# MCU.net
KiCad netlist of a schematic drawn in Altium Designer
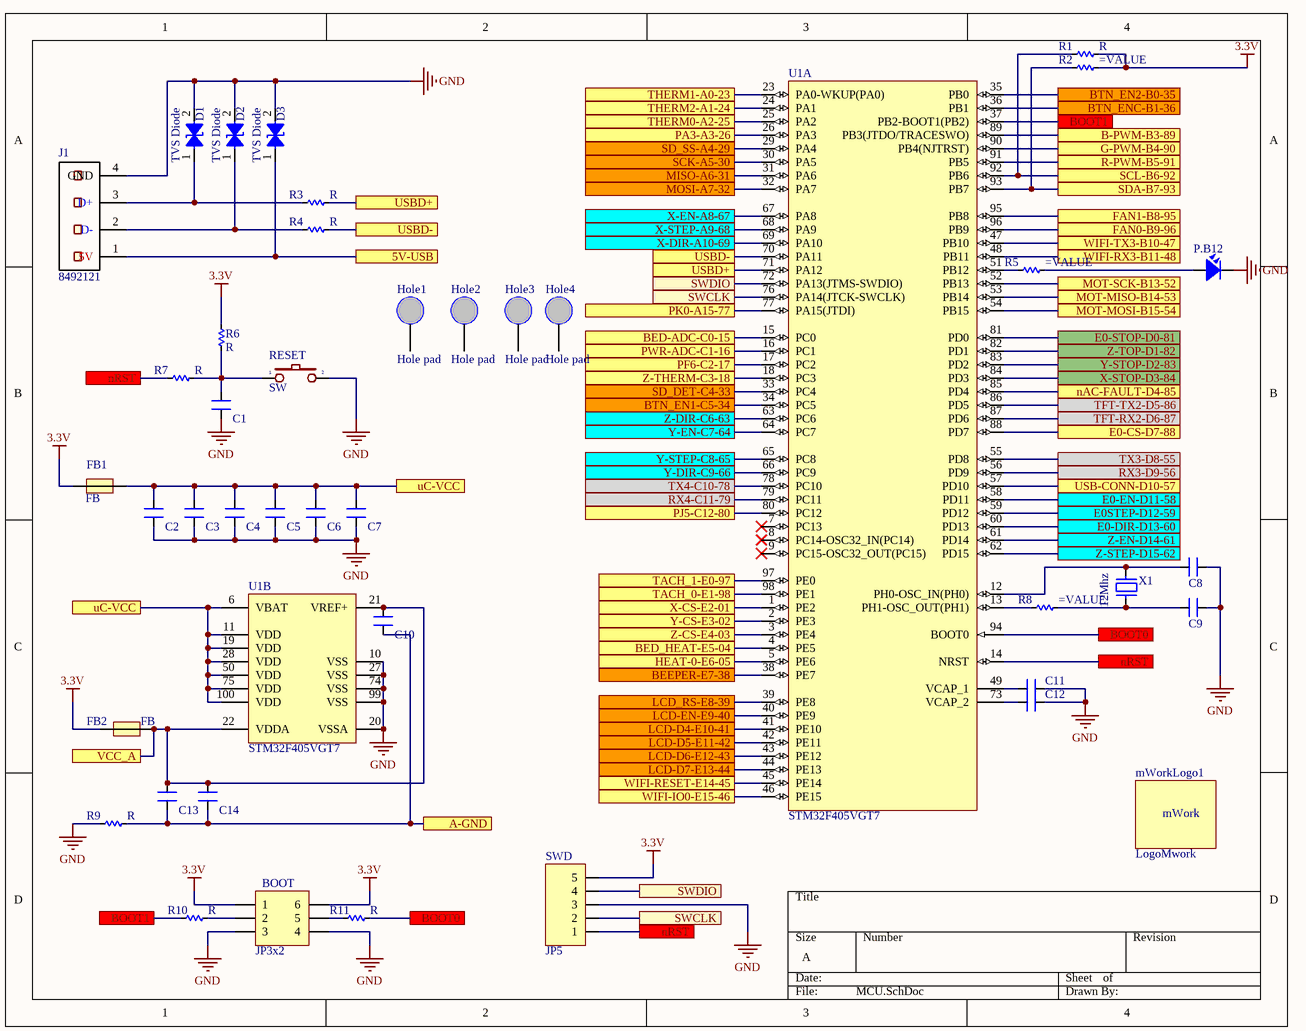
[diagram p0: MCU.SchDoc]

(export (version "E")
  (design (tool "Eeschema 10.0.6"))
  (components
    (comp (ref "BOOT")
      (value "JP3x2")
      (footprint "JP3-D2T")
      (description "WR-PHD 2.54 mm Dual Socket Header")
      (fields
        (field (name "MANUFACTURER") "Würth Elektronik eiSos GmbH")
        (field (name "PARTNO") "61300621821")
        (field (name "CREATED BY") "Karrer Zheng")
      )
      (libsource (lib "BanLinhKien") (part "JP3x2"))
    )
    (comp (ref "C1") (value "CN") (footprint "CN-SMD-0603_big") (libsource (lib "nhan") (part "CN")))
    (comp (ref "C2") (value "CN") (footprint "CN-SMD-0603_big") (libsource (lib "nhan") (part "CN")))
    (comp (ref "C3") (value "CN") (footprint "CN-SMD-0603_big") (libsource (lib "nhan") (part "CN")))
    (comp (ref "C4") (value "CN") (footprint "CN-SMD-0603_big") (libsource (lib "nhan") (part "CN")))
    (comp (ref "C5") (value "CN") (footprint "CN-SMD-0603_big") (libsource (lib "nhan") (part "CN")))
    (comp (ref "C6") (value "CN") (footprint "CN-SMD-0603_big") (libsource (lib "nhan") (part "CN")))
    (comp (ref "C7") (value "CN") (footprint "CN-SMD-0603_big") (libsource (lib "nhan") (part "CN")))
    (comp (ref "C8") (value "CN") (footprint "CN-SMD-0603_big") (libsource (lib "nhan") (part "CN")))
    (comp (ref "C9") (value "CN") (footprint "CN-SMD-0603_big") (libsource (lib "nhan") (part "CN")))
    (comp (ref "C10") (value "CN") (footprint "CN-SMD-0603_big") (libsource (lib "nhan") (part "CN")))
    (comp (ref "C11") (value "CN") (footprint "CN-SMD-0603_big") (libsource (lib "nhan") (part "CN")))
    (comp (ref "C12") (value "CN") (footprint "CN-SMD-0603_big") (libsource (lib "nhan") (part "CN")))
    (comp (ref "C13") (value "CN") (footprint "CN-SMD-0603_big") (libsource (lib "nhan") (part "CN")))
    (comp (ref "C14") (value "CN") (footprint "CN-SMD-0603_big") (libsource (lib "nhan") (part "CN")))
    (comp (ref "D1")
      (value "TVS Diode")
      (footprint "DIO-SMD-214AC")
      (description "SMAJ5.0A")
      (libsource (lib "nhan") (part "TVS Diode"))
    )
    (comp (ref "D2")
      (value "TVS Diode")
      (footprint "DIO-SMD-214AC")
      (description "SMAJ5.0A")
      (libsource (lib "nhan") (part "TVS Diode"))
    )
    (comp (ref "D3")
      (value "TVS Diode")
      (footprint "DIO-SMD-214AC")
      (description "SMAJ5.0A")
      (libsource (lib "nhan") (part "TVS Diode"))
    )
    (comp (ref "FB1") (value "FB") (footprint "Capacitor_805") (libsource (lib "nhan") (part "FB")))
    (comp (ref "FB2") (value "FB") (footprint "Capacitor_805") (libsource (lib "nhan") (part "FB")))
    (comp (ref "Hole1") (value "Hole pad") (footprint "HolePad1") (libsource (lib "nhan") (part "Hole pad")))
    (comp (ref "Hole2") (value "Hole pad") (footprint "HolePad1") (libsource (lib "nhan") (part "Hole pad")))
    (comp (ref "Hole3") (value "Hole pad") (footprint "HolePad1") (libsource (lib "nhan") (part "Hole pad")))
    (comp (ref "Hole4") (value "Hole pad") (footprint "HolePad1") (libsource (lib "nhan") (part "Hole pad")))
    (comp (ref "J1")
      (value "8492121")
      (footprint "USB-C2")
      (description "THT USB 2.0 A Connector WE-EPLE")
      (fields
        (field (name "MANUFACTURER") "Würth Elektronik eiSos GmbH")
        (field (name "CREATED BY") "Christin Otto")
      )
      (libsource (lib "nhan") (part "USB-4"))
    )
    (comp (ref "mWorkLogo1")
      (value "LogoMwork")
      (footprint "LogoMwork15*6")
      (libsource (lib "nhan") (part "LogoMwork"))
    )
    (comp (ref "P.B12") (value "LED") (footprint "LED-RED-0805") (libsource (lib "LIBRARY") (part "LED SMD")))
    (comp (ref "R1") (value "R") (footprint "RES-SMD-0603_BIG") (libsource (lib "nhan") (part "R")))
    (comp (ref "R2") (value "~") (footprint "RES-SMD-0603_BIG") (libsource (lib "nhan") (part "R")))
    (comp (ref "R3") (value "R") (footprint "RES-SMD-0603_BIG") (libsource (lib "nhan") (part "R")))
    (comp (ref "R4") (value "R") (footprint "RES-SMD-0603_BIG") (libsource (lib "nhan") (part "R")))
    (comp (ref "R5") (value "~") (footprint "RES-SMD-0603_BIG") (libsource (lib "nhan") (part "R")))
    (comp (ref "R6") (value "R") (footprint "RES-SMD-0603_BIG") (libsource (lib "nhan") (part "R")))
    (comp (ref "R7") (value "R") (footprint "RES-SMD-0603_BIG") (libsource (lib "nhan") (part "R")))
    (comp (ref "R8") (value "~") (footprint "RES-SMD-0603_BIG") (libsource (lib "nhan") (part "R")))
    (comp (ref "R9") (value "R") (footprint "RES-SMD-0603_BIG") (libsource (lib "nhan") (part "R")))
    (comp (ref "R10") (value "R") (footprint "RES-SMD-0603_BIG") (libsource (lib "nhan") (part "R")))
    (comp (ref "R11") (value "R") (footprint "RES-SMD-0603_BIG") (libsource (lib "nhan") (part "R")))
    (comp (ref "RESET")
      (value "SW")
      (footprint "SW1-SMD")
      (description "Switch button 2 pin")
      (libsource (lib "LIBRARY") (part "SW2"))
    )
    (comp (ref "SWD")
      (value "JP5")
      (footprint "JP5-D1T")
      (description "WR-PHD 2.54 mm Angled Socket Header")
      (fields
        (field (name "MANUFACTURER") "Würth Elektronik eiSos GmbH")
        (field (name "PARTNO") "613005143121")
        (field (name "CREATED BY") "Karrer Zheng")
      )
      (libsource (lib "nhan") (part "JP5"))
    )
    (comp (ref "U1")
      (value "STM32F405VGT7")
      (footprint "STM-LQFP100_N")
      (fields (field (name "MANUFACTURER") "STMicroelectronics"))
      (libsource (lib "STMicroelectronics STM32 F4") (part "STM32F405VGT7"))
    )
    (comp (ref "X1")
      (value "12Mhz")
      (footprint "XT2")
      (description "Crystal, 32.768 KHz, -40 to 85 degC, 3.2 x 1.5 x 0.9 mm SMD")
      (libsource (lib "LIBRARY") (part "XT2"))
    )
  )
  (nets
    (net (code "1") (name "/5V-USB") (class "Default")
      (node (ref "D3") (pin "1") (pinfunction "I/O_1_1") (pintype "passive"))
      (node (ref "J1") (pin "1") (pinfunction "5V_1") (pintype "passive"))
    )
    (net (code "2") (name "/A-GND") (class "Default")
      (node (ref "C10") (pin "1") (pinfunction "1_1") (pintype "passive"))
      (node (ref "C13") (pin "1") (pinfunction "1_1") (pintype "passive"))
      (node (ref "C14") (pin "1") (pinfunction "1_1") (pintype "passive"))
      (node (ref "R9") (pin "1") (pinfunction "1_1") (pintype "passive"))
    )
    (net (code "3") (name "/B-PWM-B3-89") (class "Default")
      (node (ref "U1") (pin "89") (pinfunction "PB3(JTDO/TRACESWO)_89") (pintype "bidirectional"))
    )
    (net (code "4") (name "/BED-ADC-C0-15") (class "Default")
      (node (ref "U1") (pin "15") (pinfunction "PC0_15") (pintype "bidirectional"))
    )
    (net (code "5") (name "/BED_HEAT-E5-04") (class "Default")
      (node (ref "U1") (pin "4") (pinfunction "PE5_4") (pintype "bidirectional"))
    )
    (net (code "6") (name "/BEEPER-E7-38") (class "Default")
      (node (ref "U1") (pin "38") (pinfunction "PE7_38") (pintype "bidirectional"))
    )
    (net (code "7") (name "/BOOT0") (class "Default")
      (node (ref "R11") (pin "1") (pinfunction "1_1") (pintype "passive"))
      (node (ref "U1") (pin "94") (pinfunction "BOOT0_94") (pintype "input"))
    )
    (net (code "8") (name "/BOOT1") (class "Default")
      (node (ref "R10") (pin "2") (pinfunction "2_2") (pintype "passive"))
      (node (ref "U1") (pin "37") (pinfunction "PB2-BOOT1(PB2)_37") (pintype "bidirectional"))
    )
    (net (code "9") (name "/BTN_EN1-C5-34") (class "Default")
      (node (ref "U1") (pin "34") (pinfunction "PC5_34") (pintype "bidirectional"))
    )
    (net (code "10") (name "/BTN_EN2-B0-35") (class "Default")
      (node (ref "U1") (pin "35") (pinfunction "PB0_35") (pintype "bidirectional"))
    )
    (net (code "11") (name "/BTN_ENC-B1-36") (class "Default")
      (node (ref "U1") (pin "36") (pinfunction "PB1_36") (pintype "bidirectional"))
    )
    (net (code "12") (name "/E0-CS-D7-88") (class "Default")
      (node (ref "U1") (pin "88") (pinfunction "PD7_88") (pintype "bidirectional"))
    )
    (net (code "13") (name "/E0-DIR-D13-60") (class "Default")
      (node (ref "U1") (pin "60") (pinfunction "PD13_60") (pintype "bidirectional"))
    )
    (net (code "14") (name "/E0-EN-D11-58") (class "Default")
      (node (ref "U1") (pin "58") (pinfunction "PD11_58") (pintype "bidirectional"))
    )
    (net (code "15") (name "/E0-STOP-D0-81") (class "Default")
      (node (ref "U1") (pin "81") (pinfunction "PD0_81") (pintype "bidirectional"))
    )
    (net (code "16") (name "/E0STEP-D12-59") (class "Default")
      (node (ref "U1") (pin "59") (pinfunction "PD12_59") (pintype "bidirectional"))
    )
    (net (code "17") (name "/FAN0-B9-96") (class "Default")
      (node (ref "U1") (pin "96") (pinfunction "PB9_96") (pintype "bidirectional"))
    )
    (net (code "18") (name "/FAN1-B8-95") (class "Default")
      (node (ref "U1") (pin "95") (pinfunction "PB8_95") (pintype "bidirectional"))
    )
    (net (code "19") (name "/G-PWM-B4-90") (class "Default")
      (node (ref "U1") (pin "90") (pinfunction "PB4(NJTRST)_90") (pintype "bidirectional"))
    )
    (net (code "20") (name "/HEAT-0-E6-05") (class "Default")
      (node (ref "U1") (pin "5") (pinfunction "PE6_5") (pintype "bidirectional"))
    )
    (net (code "21") (name "/LCD-D4-E10-41") (class "Default")
      (node (ref "U1") (pin "41") (pinfunction "PE10_41") (pintype "bidirectional"))
    )
    (net (code "22") (name "/LCD-D5-E11-42") (class "Default")
      (node (ref "U1") (pin "42") (pinfunction "PE11_42") (pintype "bidirectional"))
    )
    (net (code "23") (name "/LCD-D6-E12-43") (class "Default")
      (node (ref "U1") (pin "43") (pinfunction "PE12_43") (pintype "bidirectional"))
    )
    (net (code "24") (name "/LCD-D7-E13-44") (class "Default")
      (node (ref "U1") (pin "44") (pinfunction "PE13_44") (pintype "bidirectional"))
    )
    (net (code "25") (name "/LCD-EN-E9-40") (class "Default")
      (node (ref "U1") (pin "40") (pinfunction "PE9_40") (pintype "bidirectional"))
    )
    (net (code "26") (name "/LCD_RS-E8-39") (class "Default")
      (node (ref "U1") (pin "39") (pinfunction "PE8_39") (pintype "bidirectional"))
    )
    (net (code "27") (name "/MISO-A6-31") (class "Default")
      (node (ref "U1") (pin "31") (pinfunction "PA6_31") (pintype "bidirectional"))
    )
    (net (code "28") (name "/MOSI-A7-32") (class "Default")
      (node (ref "U1") (pin "32") (pinfunction "PA7_32") (pintype "bidirectional"))
    )
    (net (code "29") (name "/MOT-MISO-B14-53") (class "Default")
      (node (ref "U1") (pin "53") (pinfunction "PB14_53") (pintype "bidirectional"))
    )
    (net (code "30") (name "/MOT-MOSI-B15-54") (class "Default")
      (node (ref "U1") (pin "54") (pinfunction "PB15_54") (pintype "bidirectional"))
    )
    (net (code "31") (name "/MOT-SCK-B13-52") (class "Default")
      (node (ref "U1") (pin "52") (pinfunction "PB13_52") (pintype "bidirectional"))
    )
    (net (code "32") (name "/PA3-A3-26") (class "Default")
      (node (ref "U1") (pin "26") (pinfunction "PA3_26") (pintype "bidirectional"))
    )
    (net (code "33") (name "/PF6-C2-17") (class "Default")
      (node (ref "U1") (pin "17") (pinfunction "PC2_17") (pintype "bidirectional"))
    )
    (net (code "34") (name "/PJ5-C12-80") (class "Default")
      (node (ref "U1") (pin "80") (pinfunction "PC12_80") (pintype "bidirectional"))
    )
    (net (code "35") (name "/PK0-A15-77") (class "Default")
      (node (ref "U1") (pin "77") (pinfunction "PA15(JTDI)_77") (pintype "bidirectional"))
    )
    (net (code "36") (name "/PWR-ADC-C1-16") (class "Default")
      (node (ref "U1") (pin "16") (pinfunction "PC1_16") (pintype "bidirectional"))
    )
    (net (code "37") (name "/R-PWM-B5-91") (class "Default")
      (node (ref "U1") (pin "91") (pinfunction "PB5_91") (pintype "bidirectional"))
    )
    (net (code "38") (name "/RX3-D9-56") (class "Default")
      (node (ref "U1") (pin "56") (pinfunction "PD9_56") (pintype "bidirectional"))
    )
    (net (code "39") (name "/RX4-C11-79") (class "Default")
      (node (ref "U1") (pin "79") (pinfunction "PC11_79") (pintype "bidirectional"))
    )
    (net (code "40") (name "/SCK-A5-30") (class "Default")
      (node (ref "U1") (pin "30") (pinfunction "PA5_30") (pintype "bidirectional"))
    )
    (net (code "41") (name "/SCL-B6-92") (class "Default")
      (node (ref "R1") (pin "1") (pinfunction "1_1") (pintype "passive"))
      (node (ref "U1") (pin "92") (pinfunction "PB6_92") (pintype "bidirectional"))
    )
    (net (code "42") (name "/SDA-B7-93") (class "Default")
      (node (ref "R2") (pin "1") (pinfunction "1_1") (pintype "passive"))
      (node (ref "U1") (pin "93") (pinfunction "PB7_93") (pintype "bidirectional"))
    )
    (net (code "43") (name "/SD_DET-C4-33") (class "Default")
      (node (ref "U1") (pin "33") (pinfunction "PC4_33") (pintype "bidirectional"))
    )
    (net (code "44") (name "/SD_SS-A4-29") (class "Default")
      (node (ref "U1") (pin "29") (pinfunction "PA4_29") (pintype "bidirectional"))
    )
    (net (code "45") (name "/SWCLK") (class "Default")
      (node (ref "SWD") (pin "2") (pinfunction "2_2") (pintype "passive"))
      (node (ref "U1") (pin "76") (pinfunction "PA14(JTCK-SWCLK)_76") (pintype "bidirectional"))
    )
    (net (code "46") (name "/SWDIO") (class "Default")
      (node (ref "SWD") (pin "4") (pinfunction "4_4") (pintype "passive"))
      (node (ref "U1") (pin "72") (pinfunction "PA13(JTMS-SWDIO)_72") (pintype "bidirectional"))
    )
    (net (code "47") (name "/TACH_0-E1-98") (class "Default")
      (node (ref "U1") (pin "98") (pinfunction "PE1_98") (pintype "bidirectional"))
    )
    (net (code "48") (name "/TACH_1-E0-97") (class "Default")
      (node (ref "U1") (pin "97") (pinfunction "PE0_97") (pintype "bidirectional"))
    )
    (net (code "49") (name "/TFT-RX2-D6-87") (class "Default")
      (node (ref "U1") (pin "87") (pinfunction "PD6_87") (pintype "bidirectional"))
    )
    (net (code "50") (name "/TFT-TX2-D5-86") (class "Default")
      (node (ref "U1") (pin "86") (pinfunction "PD5_86") (pintype "bidirectional"))
    )
    (net (code "51") (name "/THERM0-A2-25") (class "Default")
      (node (ref "U1") (pin "25") (pinfunction "PA2_25") (pintype "bidirectional"))
    )
    (net (code "52") (name "/THERM1-A0-23") (class "Default")
      (node (ref "U1") (pin "23") (pinfunction "PA0-WKUP(PA0)_23") (pintype "bidirectional"))
    )
    (net (code "53") (name "/THERM2-A1-24") (class "Default")
      (node (ref "U1") (pin "24") (pinfunction "PA1_24") (pintype "bidirectional"))
    )
    (net (code "54") (name "/TX3-D8-55") (class "Default")
      (node (ref "U1") (pin "55") (pinfunction "PD8_55") (pintype "bidirectional"))
    )
    (net (code "55") (name "/TX4-C10-78") (class "Default")
      (node (ref "U1") (pin "78") (pinfunction "PC10_78") (pintype "bidirectional"))
    )
    (net (code "56") (name "/USB-CONN-D10-57") (class "Default")
      (node (ref "U1") (pin "57") (pinfunction "PD10_57") (pintype "bidirectional"))
    )
    (net (code "57") (name "/USBD+") (class "Default")
      (node (ref "R3") (pin "1") (pinfunction "1_1") (pintype "passive"))
      (node (ref "U1") (pin "71") (pinfunction "PA12_71") (pintype "bidirectional"))
    )
    (net (code "58") (name "/USBD-") (class "Default")
      (node (ref "R4") (pin "1") (pinfunction "1_1") (pintype "passive"))
      (node (ref "U1") (pin "70") (pinfunction "PA11_70") (pintype "bidirectional"))
    )
    (net (code "59") (name "/VCC_A") (class "Default")
      (node (ref "C10") (pin "2") (pinfunction "2_2") (pintype "passive"))
      (node (ref "C13") (pin "2") (pinfunction "2_2") (pintype "passive"))
      (node (ref "C14") (pin "2") (pinfunction "2_2") (pintype "passive"))
      (node (ref "FB2") (pin "2") (pinfunction "2_2") (pintype "passive"))
      (node (ref "U1") (pin "21") (pinfunction "VREF+_21") (pintype "power_in"))
      (node (ref "U1") (pin "22") (pinfunction "VDDA_22") (pintype "power_in"))
    )
    (net (code "60") (name "/WIFI-IO0-E15-46") (class "Default")
      (node (ref "U1") (pin "46") (pinfunction "PE15_46") (pintype "bidirectional"))
    )
    (net (code "61") (name "/WIFI-RESET-E14-45") (class "Default")
      (node (ref "U1") (pin "45") (pinfunction "PE14_45") (pintype "bidirectional"))
    )
    (net (code "62") (name "/WIFI-RX3-B11-48") (class "Default")
      (node (ref "U1") (pin "48") (pinfunction "PB11_48") (pintype "bidirectional"))
    )
    (net (code "63") (name "/WIFI-TX3-B10-47") (class "Default")
      (node (ref "U1") (pin "47") (pinfunction "PB10_47") (pintype "bidirectional"))
    )
    (net (code "64") (name "/X-CS-E2-01") (class "Default")
      (node (ref "U1") (pin "1") (pinfunction "PE2_1") (pintype "bidirectional"))
    )
    (net (code "65") (name "/X-DIR-A10-69") (class "Default")
      (node (ref "U1") (pin "69") (pinfunction "PA10_69") (pintype "bidirectional"))
    )
    (net (code "66") (name "/X-EN-A8-67") (class "Default")
      (node (ref "U1") (pin "67") (pinfunction "PA8_67") (pintype "bidirectional"))
    )
    (net (code "67") (name "/X-STEP-A9-68") (class "Default")
      (node (ref "U1") (pin "68") (pinfunction "PA9_68") (pintype "bidirectional"))
    )
    (net (code "68") (name "/X-STOP-D3-84") (class "Default")
      (node (ref "U1") (pin "84") (pinfunction "PD3_84") (pintype "bidirectional"))
    )
    (net (code "69") (name "/Y-CS-E3-02") (class "Default")
      (node (ref "U1") (pin "2") (pinfunction "PE3_2") (pintype "bidirectional"))
    )
    (net (code "70") (name "/Y-DIR-C9-66") (class "Default")
      (node (ref "U1") (pin "66") (pinfunction "PC9_66") (pintype "bidirectional"))
    )
    (net (code "71") (name "/Y-EN-C7-64") (class "Default")
      (node (ref "U1") (pin "64") (pinfunction "PC7_64") (pintype "bidirectional"))
    )
    (net (code "72") (name "/Y-STEP-C8-65") (class "Default")
      (node (ref "U1") (pin "65") (pinfunction "PC8_65") (pintype "bidirectional"))
    )
    (net (code "73") (name "/Y-STOP-D2-83") (class "Default")
      (node (ref "U1") (pin "83") (pinfunction "PD2_83") (pintype "bidirectional"))
    )
    (net (code "74") (name "/Z-CS-E4-03") (class "Default")
      (node (ref "U1") (pin "3") (pinfunction "PE4_3") (pintype "bidirectional"))
    )
    (net (code "75") (name "/Z-DIR-C6-63") (class "Default")
      (node (ref "U1") (pin "63") (pinfunction "PC6_63") (pintype "bidirectional"))
    )
    (net (code "76") (name "/Z-EN-D14-61") (class "Default")
      (node (ref "U1") (pin "61") (pinfunction "PD14_61") (pintype "bidirectional"))
    )
    (net (code "77") (name "/Z-STEP-D15-62") (class "Default")
      (node (ref "U1") (pin "62") (pinfunction "PD15_62") (pintype "bidirectional"))
    )
    (net (code "78") (name "/Z-THERM-C3-18") (class "Default")
      (node (ref "U1") (pin "18") (pinfunction "PC3_18") (pintype "bidirectional"))
    )
    (net (code "79") (name "/Z-TOP-D1-82") (class "Default")
      (node (ref "U1") (pin "82") (pinfunction "PD1_82") (pintype "bidirectional"))
    )
    (net (code "80") (name "/nAC-FAULT-D4-85") (class "Default")
      (node (ref "U1") (pin "85") (pinfunction "PD4_85") (pintype "bidirectional"))
    )
    (net (code "81") (name "/nRST") (class "Default")
      (node (ref "R7") (pin "2") (pinfunction "2_2") (pintype "passive"))
      (node (ref "SWD") (pin "1") (pinfunction "1_1") (pintype "passive"))
      (node (ref "U1") (pin "14") (pinfunction "NRST_14") (pintype "bidirectional"))
    )
    (net (code "82") (name "/uC-VCC") (class "Default")
      (node (ref "C2") (pin "2") (pinfunction "2_2") (pintype "passive"))
      (node (ref "C3") (pin "2") (pinfunction "2_2") (pintype "passive"))
      (node (ref "C4") (pin "2") (pinfunction "2_2") (pintype "passive"))
      (node (ref "C5") (pin "2") (pinfunction "2_2") (pintype "passive"))
      (node (ref "C6") (pin "2") (pinfunction "2_2") (pintype "passive"))
      (node (ref "C7") (pin "2") (pinfunction "2_2") (pintype "passive"))
      (node (ref "FB1") (pin "2") (pinfunction "2_2") (pintype "passive"))
      (node (ref "U1") (pin "100") (pinfunction "VDD_100") (pintype "power_in"))
      (node (ref "U1") (pin "11") (pinfunction "VDD_11") (pintype "power_in"))
      (node (ref "U1") (pin "19") (pinfunction "VDD_19") (pintype "power_in"))
      (node (ref "U1") (pin "28") (pinfunction "VDD_28") (pintype "power_in"))
      (node (ref "U1") (pin "50") (pinfunction "VDD_50") (pintype "power_in"))
      (node (ref "U1") (pin "6") (pinfunction "VBAT_6") (pintype "power_in"))
      (node (ref "U1") (pin "75") (pinfunction "VDD_75") (pintype "power_in"))
    )
    (net (code "83") (name "3.3V") (class "Default")
      (node (ref "BOOT") (pin "1") (pinfunction "1_1") (pintype "passive"))
      (node (ref "BOOT") (pin "6") (pinfunction "6_6") (pintype "passive"))
      (node (ref "FB1") (pin "1") (pinfunction "1_1") (pintype "passive"))
      (node (ref "FB2") (pin "1") (pinfunction "1_1") (pintype "passive"))
      (node (ref "R1") (pin "2") (pinfunction "2_2") (pintype "passive"))
      (node (ref "R2") (pin "2") (pinfunction "2_2") (pintype "passive"))
      (node (ref "R6") (pin "1") (pinfunction "1_1") (pintype "passive"))
      (node (ref "SWD") (pin "5") (pinfunction "5_5") (pintype "passive"))
    )
    (net (code "84") (name "GND") (class "Default")
      (node (ref "BOOT") (pin "3") (pinfunction "3_3") (pintype "passive"))
      (node (ref "BOOT") (pin "4") (pinfunction "4_4") (pintype "passive"))
      (node (ref "C1") (pin "1") (pinfunction "1_1") (pintype "passive"))
      (node (ref "C11") (pin "2") (pinfunction "2_2") (pintype "passive"))
      (node (ref "C12") (pin "2") (pinfunction "2_2") (pintype "passive"))
      (node (ref "C2") (pin "1") (pinfunction "1_1") (pintype "passive"))
      (node (ref "C3") (pin "1") (pinfunction "1_1") (pintype "passive"))
      (node (ref "C4") (pin "1") (pinfunction "1_1") (pintype "passive"))
      (node (ref "C5") (pin "1") (pinfunction "1_1") (pintype "passive"))
      (node (ref "C6") (pin "1") (pinfunction "1_1") (pintype "passive"))
      (node (ref "C7") (pin "1") (pinfunction "1_1") (pintype "passive"))
      (node (ref "C8") (pin "2") (pinfunction "2_2") (pintype "passive"))
      (node (ref "C9") (pin "2") (pinfunction "2_2") (pintype "passive"))
      (node (ref "D1") (pin "2") (pinfunction "GND_2") (pintype "passive"))
      (node (ref "D2") (pin "2") (pinfunction "GND_2") (pintype "passive"))
      (node (ref "D3") (pin "2") (pinfunction "GND_2") (pintype "passive"))
      (node (ref "J1") (pin "4") (pinfunction "GND_4") (pintype "passive"))
      (node (ref "P.B12") (pin "2") (pinfunction "2_2") (pintype "passive"))
      (node (ref "R9") (pin "2") (pinfunction "2_2") (pintype "passive"))
      (node (ref "RESET") (pin "2") (pinfunction "2_2") (pintype "passive"))
      (node (ref "SWD") (pin "3") (pinfunction "3_3") (pintype "passive"))
      (node (ref "U1") (pin "10") (pinfunction "VSS_10") (pintype "power_in"))
      (node (ref "U1") (pin "20") (pinfunction "VSSA_20") (pintype "power_in"))
      (node (ref "U1") (pin "27") (pinfunction "VSS_27") (pintype "power_in"))
      (node (ref "U1") (pin "74") (pinfunction "VSS_74") (pintype "power_in"))
      (node (ref "U1") (pin "99") (pinfunction "VSS_99") (pintype "power_in"))
    )
    (net (code "85") (name "Net-(BOOT-Pad2)") (class "Default")
      (node (ref "BOOT") (pin "2") (pinfunction "2_2") (pintype "passive"))
      (node (ref "R10") (pin "1") (pinfunction "1_1") (pintype "passive"))
    )
    (net (code "86") (name "Net-(BOOT-Pad5)") (class "Default")
      (node (ref "BOOT") (pin "5") (pinfunction "5_5") (pintype "passive"))
      (node (ref "R11") (pin "2") (pinfunction "2_2") (pintype "passive"))
    )
    (net (code "87") (name "Net-(C1-Pad2)") (class "Default")
      (node (ref "C1") (pin "2") (pinfunction "2_2") (pintype "passive"))
      (node (ref "R6") (pin "2") (pinfunction "2_2") (pintype "passive"))
      (node (ref "R7") (pin "1") (pinfunction "1_1") (pintype "passive"))
      (node (ref "RESET") (pin "1") (pinfunction "1_1") (pintype "passive"))
    )
    (net (code "88") (name "Net-(C9-Pad1)") (class "Default")
      (node (ref "C9") (pin "1") (pinfunction "1_1") (pintype "passive"))
      (node (ref "R8") (pin "2") (pinfunction "2_2") (pintype "passive"))
      (node (ref "X1") (pin "1") (pinfunction "1_1") (pintype "passive"))
    )
    (net (code "89") (name "Net-(D1-I{slash}O_1)") (class "Default")
      (node (ref "D1") (pin "1") (pinfunction "I/O_1_1") (pintype "passive"))
      (node (ref "J1") (pin "3") (pinfunction "D+_3") (pintype "passive"))
      (node (ref "R3") (pin "2") (pinfunction "2_2") (pintype "passive"))
    )
    (net (code "90") (name "Net-(D2-I{slash}O_1)") (class "Default")
      (node (ref "D2") (pin "1") (pinfunction "I/O_1_1") (pintype "passive"))
      (node (ref "J1") (pin "2") (pinfunction "D-_2") (pintype "passive"))
      (node (ref "R4") (pin "2") (pinfunction "2_2") (pintype "passive"))
    )
    (net (code "91") (name "Net-(P.B12-Pad1)") (class "Default")
      (node (ref "P.B12") (pin "1") (pinfunction "1_1") (pintype "passive"))
      (node (ref "R5") (pin "2") (pinfunction "2_2") (pintype "passive"))
    )
    (net (code "92") (name "Net-(U1A-PB12)") (class "Default")
      (node (ref "R5") (pin "1") (pinfunction "1_1") (pintype "passive"))
      (node (ref "U1") (pin "51") (pinfunction "PB12_51") (pintype "bidirectional"))
    )
    (net (code "93") (name "Net-(U1A-PH0-OSC_IN(PH0))") (class "Default")
      (node (ref "C8") (pin "1") (pinfunction "1_1") (pintype "passive"))
      (node (ref "U1") (pin "12") (pinfunction "PH0-OSC_IN(PH0)_12") (pintype "bidirectional"))
      (node (ref "X1") (pin "2") (pinfunction "2_2") (pintype "passive"))
    )
    (net (code "94") (name "Net-(U1A-PH1-OSC_OUT(PH1))") (class "Default")
      (node (ref "R8") (pin "1") (pinfunction "1_1") (pintype "passive"))
      (node (ref "U1") (pin "13") (pinfunction "PH1-OSC_OUT(PH1)_13") (pintype "bidirectional"))
    )
    (net (code "95") (name "Net-(U1A-VCAP_1)") (class "Default")
      (node (ref "C11") (pin "1") (pinfunction "1_1") (pintype "passive"))
      (node (ref "U1") (pin "49") (pinfunction "VCAP_1_49") (pintype "power_in"))
    )
    (net (code "96") (name "Net-(U1A-VCAP_2)") (class "Default")
      (node (ref "C12") (pin "1") (pinfunction "1_1") (pintype "passive"))
      (node (ref "U1") (pin "73") (pinfunction "VCAP_2_73") (pintype "power_in"))
    )
    (net (code "97") (name "unconnected-(Hole1-Pad1)") (class "Default")
      (node (ref "Hole1") (pin "1") (pinfunction "1_1") (pintype "passive"))
    )
    (net (code "98") (name "unconnected-(Hole2-Pad1)") (class "Default")
      (node (ref "Hole2") (pin "1") (pinfunction "1_1") (pintype "passive"))
    )
    (net (code "99") (name "unconnected-(Hole3-Pad1)") (class "Default")
      (node (ref "Hole3") (pin "1") (pinfunction "1_1") (pintype "passive"))
    )
    (net (code "100") (name "unconnected-(Hole4-Pad1)") (class "Default")
      (node (ref "Hole4") (pin "1") (pinfunction "1_1") (pintype "passive"))
    )
    (net (code "101") (name "unconnected-(U1A-PC13-Pad7)") (class "Default")
      (node (ref "U1") (pin "7") (pinfunction "PC13_7") (pintype "bidirectional+no_connect"))
    )
    (net (code "102") (name "unconnected-(U1A-PC14-OSC32_IN(PC14)-Pad8)") (class "Default")
      (node (ref "U1") (pin "8") (pinfunction "PC14-OSC32_IN(PC14)_8") (pintype "bidirectional+no_connect"))
    )
    (net (code "103") (name "unconnected-(U1A-PC15-OSC32_OUT(PC15)-Pad9)") (class "Default")
      (node (ref "U1") (pin "9") (pinfunction "PC15-OSC32_OUT(PC15)_9") (pintype "bidirectional+no_connect"))
    )
  )
)
